# design.net
KiCad netlist of a schematic drawn in Altium Designer
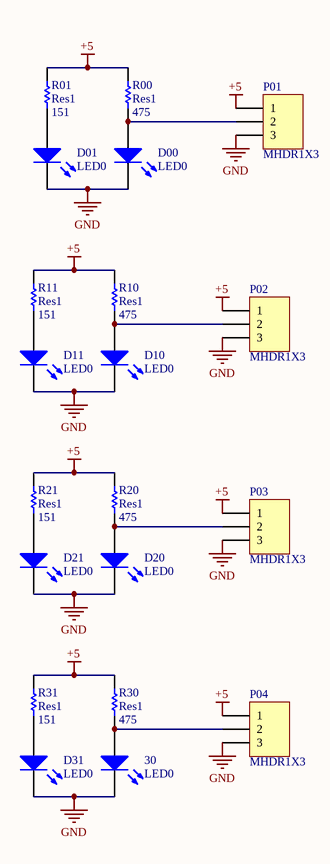
[diagram p0: 红外模块.SchDoc]

(export (version "E")
  (design (tool "Eeschema 10.0.6"))
  (components
    (comp (ref "30")
      (value "LED0")
      (footprint "LED-0")
      (description "Typical INFRARED GaAs LED")
      (fields (field (name "PUBLISHER") "Altium Limited"))
      (libsource (lib "Miscellaneous Devices") (part "LED0"))
    )
    (comp (ref "D00")
      (value "LED0")
      (footprint "LED-0")
      (description "Typical INFRARED GaAs LED")
      (fields (field (name "PUBLISHER") "Altium Limited"))
      (libsource (lib "Miscellaneous Devices") (part "LED0"))
    )
    (comp (ref "D01")
      (value "LED0")
      (footprint "LED-0")
      (description "Typical INFRARED GaAs LED")
      (fields (field (name "PUBLISHER") "Altium Limited"))
      (libsource (lib "Miscellaneous Devices") (part "LED0"))
    )
    (comp (ref "D10")
      (value "LED0")
      (footprint "LED-0")
      (description "Typical INFRARED GaAs LED")
      (fields (field (name "PUBLISHER") "Altium Limited"))
      (libsource (lib "Miscellaneous Devices") (part "LED0"))
    )
    (comp (ref "D11")
      (value "LED0")
      (footprint "LED-0")
      (description "Typical INFRARED GaAs LED")
      (fields (field (name "PUBLISHER") "Altium Limited"))
      (libsource (lib "Miscellaneous Devices") (part "LED0"))
    )
    (comp (ref "D20")
      (value "LED0")
      (footprint "LED-0")
      (description "Typical INFRARED GaAs LED")
      (fields (field (name "PUBLISHER") "Altium Limited"))
      (libsource (lib "Miscellaneous Devices") (part "LED0"))
    )
    (comp (ref "D21")
      (value "LED0")
      (footprint "LED-0")
      (description "Typical INFRARED GaAs LED")
      (fields (field (name "PUBLISHER") "Altium Limited"))
      (libsource (lib "Miscellaneous Devices") (part "LED0"))
    )
    (comp (ref "D31")
      (value "LED0")
      (footprint "LED-0")
      (description "Typical INFRARED GaAs LED")
      (fields (field (name "PUBLISHER") "Altium Limited"))
      (libsource (lib "Miscellaneous Devices") (part "LED0"))
    )
    (comp (ref "P01")
      (value "MHDR1X3")
      (footprint "MHDR1X3")
      (description "Header, 3-Pin")
      (fields (field (name "PUBLISHER") "Altium Limited"))
      (libsource (lib "Miscellaneous Connectors") (part "MHDR1X3"))
    )
    (comp (ref "P02")
      (value "MHDR1X3")
      (footprint "MHDR1X3")
      (description "Header, 3-Pin")
      (fields (field (name "PUBLISHER") "Altium Limited"))
      (libsource (lib "Miscellaneous Connectors") (part "MHDR1X3"))
    )
    (comp (ref "P03")
      (value "MHDR1X3")
      (footprint "MHDR1X3")
      (description "Header, 3-Pin")
      (fields (field (name "PUBLISHER") "Altium Limited"))
      (libsource (lib "Miscellaneous Connectors") (part "MHDR1X3"))
    )
    (comp (ref "P04")
      (value "MHDR1X3")
      (footprint "MHDR1X3")
      (description "Header, 3-Pin")
      (fields (field (name "PUBLISHER") "Altium Limited"))
      (libsource (lib "Miscellaneous Connectors") (part "MHDR1X3"))
    )
    (comp (ref "R00")
      (value "Res1")
      (footprint "AXIAL-0.3")
      (description "Resistor")
      (fields (field (name "ALTIUM_VALUE") "475") (field (name "PUBLISHER") "Altium Limited"))
      (libsource (lib "Miscellaneous Devices") (part "Res1"))
    )
    (comp (ref "R01")
      (value "Res1")
      (footprint "AXIAL-0.3")
      (description "Resistor")
      (fields (field (name "ALTIUM_VALUE") "151") (field (name "PUBLISHER") "Altium Limited"))
      (libsource (lib "Miscellaneous Devices") (part "Res1"))
    )
    (comp (ref "R10")
      (value "Res1")
      (footprint "AXIAL-0.3")
      (description "Resistor")
      (fields (field (name "ALTIUM_VALUE") "475") (field (name "PUBLISHER") "Altium Limited"))
      (libsource (lib "Miscellaneous Devices") (part "Res1"))
    )
    (comp (ref "R11")
      (value "Res1")
      (footprint "AXIAL-0.3")
      (description "Resistor")
      (fields (field (name "ALTIUM_VALUE") "151") (field (name "PUBLISHER") "Altium Limited"))
      (libsource (lib "Miscellaneous Devices") (part "Res1"))
    )
    (comp (ref "R20")
      (value "Res1")
      (footprint "AXIAL-0.3")
      (description "Resistor")
      (fields (field (name "ALTIUM_VALUE") "475") (field (name "PUBLISHER") "Altium Limited"))
      (libsource (lib "Miscellaneous Devices") (part "Res1"))
    )
    (comp (ref "R21")
      (value "Res1")
      (footprint "AXIAL-0.3")
      (description "Resistor")
      (fields (field (name "ALTIUM_VALUE") "151") (field (name "PUBLISHER") "Altium Limited"))
      (libsource (lib "Miscellaneous Devices") (part "Res1"))
    )
    (comp (ref "R30")
      (value "Res1")
      (footprint "AXIAL-0.3")
      (description "Resistor")
      (fields (field (name "ALTIUM_VALUE") "475") (field (name "PUBLISHER") "Altium Limited"))
      (libsource (lib "Miscellaneous Devices") (part "Res1"))
    )
    (comp (ref "R31")
      (value "Res1")
      (footprint "AXIAL-0.3")
      (description "Resistor")
      (fields (field (name "ALTIUM_VALUE") "151") (field (name "PUBLISHER") "Altium Limited"))
      (libsource (lib "Miscellaneous Devices") (part "Res1"))
    )
  )
  (nets
    (net (code "1") (name "+5") (class "Default")
      (node (ref "P01") (pin "1") (pinfunction "1_1") (pintype "passive"))
      (node (ref "P02") (pin "1") (pinfunction "1_1") (pintype "passive"))
      (node (ref "P03") (pin "1") (pinfunction "1_1") (pintype "passive"))
      (node (ref "P04") (pin "1") (pinfunction "1_1") (pintype "passive"))
      (node (ref "R00") (pin "2") (pinfunction "2_2") (pintype "passive"))
      (node (ref "R01") (pin "2") (pinfunction "2_2") (pintype "passive"))
      (node (ref "R10") (pin "2") (pinfunction "2_2") (pintype "passive"))
      (node (ref "R11") (pin "2") (pinfunction "2_2") (pintype "passive"))
      (node (ref "R20") (pin "2") (pinfunction "2_2") (pintype "passive"))
      (node (ref "R21") (pin "2") (pinfunction "2_2") (pintype "passive"))
      (node (ref "R30") (pin "2") (pinfunction "2_2") (pintype "passive"))
      (node (ref "R31") (pin "2") (pinfunction "2_2") (pintype "passive"))
    )
    (net (code "2") (name "GND") (class "Default")
      (node (ref "30") (pin "2") (pinfunction "K_2") (pintype "passive"))
      (node (ref "D00") (pin "2") (pinfunction "K_2") (pintype "passive"))
      (node (ref "D01") (pin "2") (pinfunction "K_2") (pintype "passive"))
      (node (ref "D10") (pin "2") (pinfunction "K_2") (pintype "passive"))
      (node (ref "D11") (pin "2") (pinfunction "K_2") (pintype "passive"))
      (node (ref "D20") (pin "2") (pinfunction "K_2") (pintype "passive"))
      (node (ref "D21") (pin "2") (pinfunction "K_2") (pintype "passive"))
      (node (ref "D31") (pin "2") (pinfunction "K_2") (pintype "passive"))
      (node (ref "P01") (pin "3") (pinfunction "3_3") (pintype "passive"))
      (node (ref "P02") (pin "3") (pinfunction "3_3") (pintype "passive"))
      (node (ref "P03") (pin "3") (pinfunction "3_3") (pintype "passive"))
      (node (ref "P04") (pin "3") (pinfunction "3_3") (pintype "passive"))
    )
    (net (code "3") (name "Net-(30-A)") (class "Default")
      (node (ref "30") (pin "1") (pinfunction "A_1") (pintype "passive"))
      (node (ref "P04") (pin "2") (pinfunction "2_2") (pintype "passive"))
      (node (ref "R30") (pin "1") (pinfunction "1_1") (pintype "passive"))
    )
    (net (code "4") (name "Net-(D00-A)") (class "Default")
      (node (ref "D00") (pin "1") (pinfunction "A_1") (pintype "passive"))
      (node (ref "P01") (pin "2") (pinfunction "2_2") (pintype "passive"))
      (node (ref "R00") (pin "1") (pinfunction "1_1") (pintype "passive"))
    )
    (net (code "5") (name "Net-(D01-A)") (class "Default")
      (node (ref "D01") (pin "1") (pinfunction "A_1") (pintype "passive"))
      (node (ref "R01") (pin "1") (pinfunction "1_1") (pintype "passive"))
    )
    (net (code "6") (name "Net-(D10-A)") (class "Default")
      (node (ref "D10") (pin "1") (pinfunction "A_1") (pintype "passive"))
      (node (ref "P02") (pin "2") (pinfunction "2_2") (pintype "passive"))
      (node (ref "R10") (pin "1") (pinfunction "1_1") (pintype "passive"))
    )
    (net (code "7") (name "Net-(D11-A)") (class "Default")
      (node (ref "D11") (pin "1") (pinfunction "A_1") (pintype "passive"))
      (node (ref "R11") (pin "1") (pinfunction "1_1") (pintype "passive"))
    )
    (net (code "8") (name "Net-(D20-A)") (class "Default")
      (node (ref "D20") (pin "1") (pinfunction "A_1") (pintype "passive"))
      (node (ref "P03") (pin "2") (pinfunction "2_2") (pintype "passive"))
      (node (ref "R20") (pin "1") (pinfunction "1_1") (pintype "passive"))
    )
    (net (code "9") (name "Net-(D21-A)") (class "Default")
      (node (ref "D21") (pin "1") (pinfunction "A_1") (pintype "passive"))
      (node (ref "R21") (pin "1") (pinfunction "1_1") (pintype "passive"))
    )
    (net (code "10") (name "Net-(D31-A)") (class "Default")
      (node (ref "D31") (pin "1") (pinfunction "A_1") (pintype "passive"))
      (node (ref "R31") (pin "1") (pinfunction "1_1") (pintype "passive"))
    )
  )
)
